# lmzmv1_0.net
KiCad netlist of a schematic drawn in EAGLE
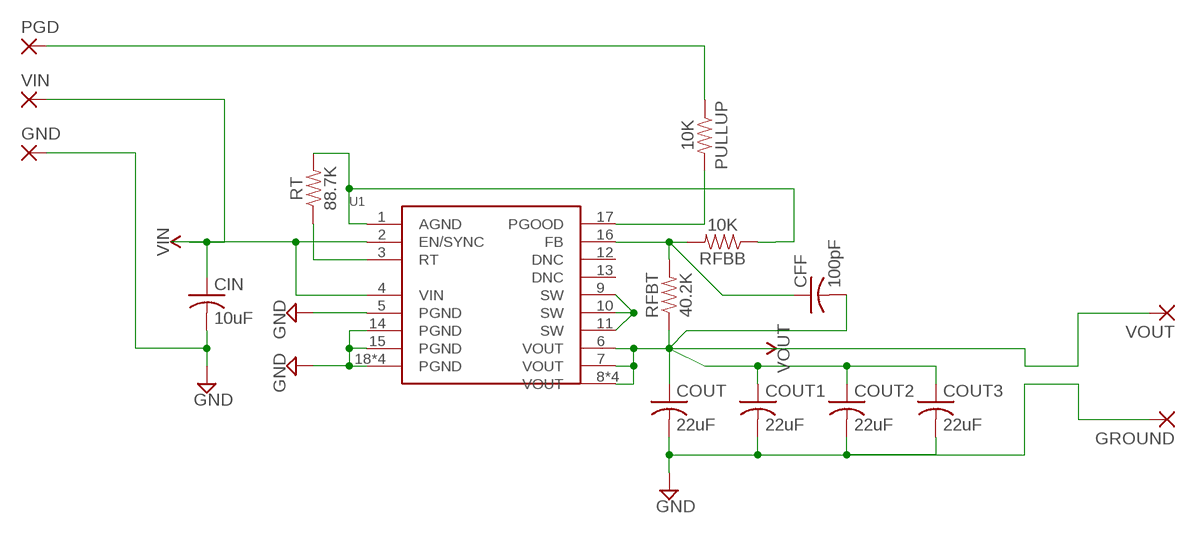
[diagram p0: schematic, sheet 1]

(export (version "E")
  (design (tool "Eeschema 10.0.6"))
  (components
    (comp (ref "CFF")
      (value "100pF")
      (footprint "eagle-import:C0603")
      (fields (field (name "MF") "YAGEO") (field (name "MPN") "CC0603JRNPO9BN101"))
      (libsource (lib "eagle-import") (part "C-USC0603"))
    )
    (comp (ref "CIN")
      (value "10uF")
      (footprint "eagle-import:C1206")
      (fields (field (name "MF") "TAIYO YUDEN") (field (name "MPN") "LMK107BJ106MALTD"))
      (libsource (lib "eagle-import") (part "C-USC1206"))
    )
    (comp (ref "COUT")
      (value "22uF")
      (footprint "eagle-import:C0805")
      (fields (field (name "MF") "AVX") (field (name "MPN") "F980G226MMA"))
      (libsource (lib "eagle-import") (part "C-USC0805"))
    )
    (comp (ref "COUT1")
      (value "22uF")
      (footprint "eagle-import:C0805")
      (fields (field (name "MF") "AVX") (field (name "MPN") "F980G226MMA"))
      (libsource (lib "eagle-import") (part "C-USC0805"))
    )
    (comp (ref "COUT2")
      (value "22uF")
      (footprint "eagle-import:C0805")
      (fields (field (name "MF") "AVX") (field (name "MPN") "F980G226MMA"))
      (libsource (lib "eagle-import") (part "C-USC0805"))
    )
    (comp (ref "COUT3")
      (value "22uF")
      (footprint "eagle-import:C0805")
      (fields (field (name "MF") "AVX") (field (name "MPN") "F980G226MMA"))
      (libsource (lib "eagle-import") (part "C-USC0805"))
    )
    (comp (ref "GND")
      (value "SMD5")
      (footprint "eagle-import:SMD2,54-5,08")
      (libsource (lib "eagle-import") (part "SMD5"))
    )
    (comp (ref "GROUND")
      (value "SMD5")
      (footprint "eagle-import:SMD2,54-5,08")
      (libsource (lib "eagle-import") (part "SMD5"))
    )
    (comp (ref "PGD")
      (value "SMD5")
      (footprint "eagle-import:SMD2,54-5,08")
      (libsource (lib "eagle-import") (part "SMD5"))
    )
    (comp (ref "PULLUP")
      (value "10K")
      (footprint "eagle-import:0603")
      (fields (field (name "MF") "YAGEO") (field (name "MPN") "RC0603FR-0710KL"))
      (libsource (lib "eagle-import") (part "RESISTOR0603"))
    )
    (comp (ref "RFBB")
      (value "10K")
      (footprint "eagle-import:0603")
      (fields (field (name "MF") "YAGEO") (field (name "MPN") "RC0603FR-0710KL"))
      (libsource (lib "eagle-import") (part "RESISTOR0603"))
    )
    (comp (ref "RFBT")
      (value "40.2K")
      (footprint "eagle-import:0603")
      (fields (field (name "MF") "MULTICOMP PRO") (field (name "MPN") "MC0603SAF4022T5E"))
      (libsource (lib "eagle-import") (part "RESISTOR0603"))
    )
    (comp (ref "RT")
      (value "88.7K")
      (footprint "eagle-import:0603")
      (fields (field (name "MF") "PANASONIC") (field (name "MPN") "ERJ-S03D8872V"))
      (libsource (lib "eagle-import") (part "RESISTOR0603"))
    )
    (comp (ref "U1")
      (value "LMZM_MODULEQFN18TI")
      (footprint "eagle-import:QFN-18")
      (fields (field (name "MPN") "LMZM33603RLRR"))
      (libsource (lib "eagle-import") (part "LMZM_MODULEQFN18TI"))
    )
    (comp (ref "VIN")
      (value "SMD5")
      (footprint "eagle-import:SMD2,54-5,08")
      (libsource (lib "eagle-import") (part "SMD5"))
    )
    (comp (ref "VOUT")
      (value "SMD5")
      (footprint "eagle-import:SMD2,54-5,08")
      (libsource (lib "eagle-import") (part "SMD5"))
    )
  )
  (nets
    (net (code "1") (name "GND") (class "Default")
      (node (ref "CIN") (pin "2") (pinfunction "2_2") (pintype "passive"))
      (node (ref "COUT") (pin "2") (pinfunction "2_2") (pintype "passive"))
      (node (ref "COUT1") (pin "2") (pinfunction "2_2") (pintype "passive"))
      (node (ref "COUT2") (pin "2") (pinfunction "2_2") (pintype "passive"))
      (node (ref "COUT3") (pin "2") (pinfunction "2_2") (pintype "passive"))
      (node (ref "GND") (pin "1") (pinfunction "P_1") (pintype "passive"))
      (node (ref "GROUND") (pin "1") (pinfunction "P_1") (pintype "passive"))
      (node (ref "U1") (pin "14") (pinfunction "PGND_14") (pintype "power_in"))
      (node (ref "U1") (pin "15") (pinfunction "PGND_15") (pintype "power_in"))
      (node (ref "U1") (pin "18") (pinfunction "PGND_18") (pintype "power_in"))
      (node (ref "U1") (pin "5") (pinfunction "PGND_5") (pintype "power_in"))
      (node (ref "U1") (pin "W") (pinfunction "PGND_W") (pintype "power_in"))
      (node (ref "U1") (pin "W1") (pinfunction "PGND_W1") (pintype "power_in"))
      (node (ref "U1") (pin "W2") (pinfunction "PGND_W2") (pintype "power_in"))
    )
    (net (code "2") (name "Net-(PGD-P)") (class "Default")
      (node (ref "PGD") (pin "1") (pinfunction "P_1") (pintype "passive"))
      (node (ref "PULLUP") (pin "1") (pinfunction "1_1") (pintype "passive"))
    )
    (net (code "3") (name "Net-(U1-AGND)") (class "Default")
      (node (ref "RFBB") (pin "1") (pinfunction "1_1") (pintype "passive"))
      (node (ref "RT") (pin "2") (pinfunction "2_2") (pintype "passive"))
      (node (ref "U1") (pin "1") (pinfunction "AGND_1") (pintype "power_in"))
    )
    (net (code "4") (name "Net-(U1-FB)") (class "Default")
      (node (ref "CFF") (pin "1") (pinfunction "1_1") (pintype "passive"))
      (node (ref "RFBB") (pin "2") (pinfunction "2_2") (pintype "passive"))
      (node (ref "RFBT") (pin "2") (pinfunction "2_2") (pintype "passive"))
      (node (ref "U1") (pin "16") (pinfunction "FB_16") (pintype "bidirectional"))
    )
    (net (code "5") (name "Net-(U1-PGOOD)") (class "Default")
      (node (ref "PULLUP") (pin "2") (pinfunction "2_2") (pintype "passive"))
      (node (ref "U1") (pin "17") (pinfunction "PGOOD_17") (pintype "bidirectional"))
    )
    (net (code "6") (name "Net-(U1-RT)") (class "Default")
      (node (ref "RT") (pin "1") (pinfunction "1_1") (pintype "passive"))
      (node (ref "U1") (pin "3") (pinfunction "RT_3") (pintype "bidirectional"))
    )
    (net (code "7") (name "Net-(U1-SW-Pad10)") (class "Default")
      (node (ref "U1") (pin "10") (pinfunction "SW_10") (pintype "bidirectional"))
      (node (ref "U1") (pin "11") (pinfunction "SW_11") (pintype "bidirectional"))
      (node (ref "U1") (pin "9") (pinfunction "SW_9") (pintype "bidirectional"))
    )
    (net (code "8") (name "VIN") (class "Default")
      (node (ref "CIN") (pin "1") (pinfunction "1_1") (pintype "passive"))
      (node (ref "U1") (pin "2") (pinfunction "EN/SYNC_2") (pintype "bidirectional"))
      (node (ref "U1") (pin "4") (pinfunction "VIN_4") (pintype "input"))
      (node (ref "VIN") (pin "1") (pinfunction "P_1") (pintype "passive"))
    )
    (net (code "9") (name "VOUT") (class "Default")
      (node (ref "CFF") (pin "2") (pinfunction "2_2") (pintype "passive"))
      (node (ref "COUT") (pin "1") (pinfunction "1_1") (pintype "passive"))
      (node (ref "COUT1") (pin "1") (pinfunction "1_1") (pintype "passive"))
      (node (ref "COUT2") (pin "1") (pinfunction "1_1") (pintype "passive"))
      (node (ref "COUT3") (pin "1") (pinfunction "1_1") (pintype "passive"))
      (node (ref "RFBT") (pin "1") (pinfunction "1_1") (pintype "passive"))
      (node (ref "U1") (pin "6") (pinfunction "VOUT_6") (pintype "output"))
      (node (ref "U1") (pin "7") (pinfunction "VOUT_7") (pintype "output"))
      (node (ref "U1") (pin "8") (pinfunction "VOUT_8") (pintype "output"))
      (node (ref "U1") (pin "X") (pinfunction "VOUT_X") (pintype "output"))
      (node (ref "U1") (pin "X1") (pinfunction "VOUT_X1") (pintype "output"))
      (node (ref "U1") (pin "X2") (pinfunction "VOUT_X2") (pintype "output"))
      (node (ref "VOUT") (pin "1") (pinfunction "P_1") (pintype "passive"))
    )
    (net (code "10") (name "unconnected-(U1-DNC-Pad12)") (class "Default")
      (node (ref "U1") (pin "12") (pinfunction "DNC_12") (pintype "bidirectional"))
    )
    (net (code "11") (name "unconnected-(U1-DNC-Pad13)") (class "Default")
      (node (ref "U1") (pin "13") (pinfunction "DNC_13") (pintype "bidirectional"))
    )
  )
)
